# Schematic_GPS_NEOM8N.net
KiCad netlist of a schematic drawn in Altium Designer
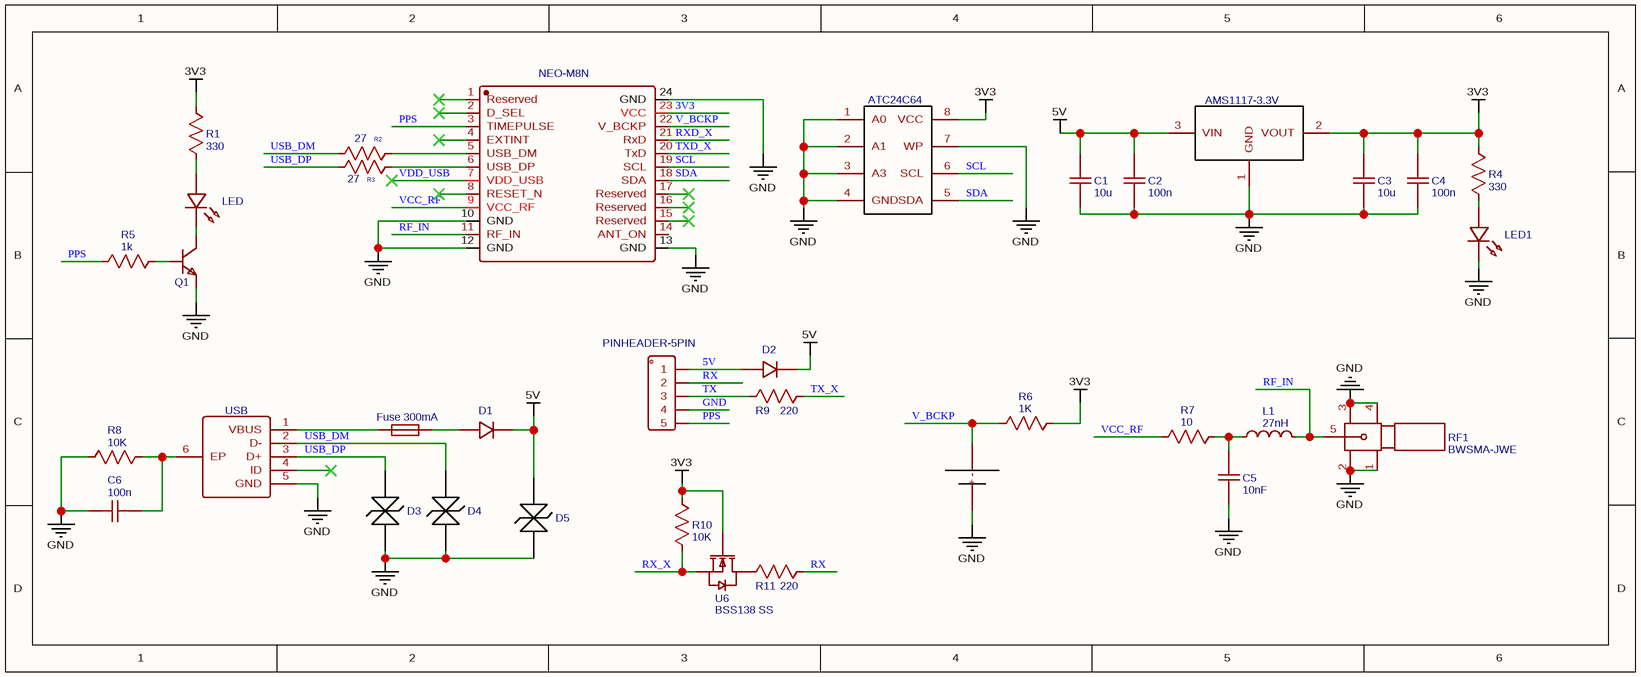
[diagram p0: Schematic_GPS NEOM8N .schdoc]

(export (version "E")
  (design (tool "Eeschema 10.0.6"))
  (components
    (comp (ref "C1")
      (value "10u")
      (fields (field (name "CONTRIBUTOR") "LCEDA_Lib"))
      (libsource (lib "altium-import") (part "root_1_10u_"))
    )
    (comp (ref "C2")
      (value "100n")
      (fields (field (name "CONTRIBUTOR") "LCEDA_Lib"))
      (libsource (lib "altium-import") (part "root_1_100n_"))
    )
    (comp (ref "C3")
      (value "10u")
      (fields (field (name "CONTRIBUTOR") "LCEDA_Lib"))
      (libsource (lib "altium-import") (part "root_1_10u_"))
    )
    (comp (ref "C4")
      (value "100n")
      (fields (field (name "CONTRIBUTOR") "LCEDA_Lib"))
      (libsource (lib "altium-import") (part "root_1_100n_"))
    )
    (comp (ref "C5")
      (value "10nF")
      (fields (field (name "CONTRIBUTOR") "EasyEDA"))
      (libsource (lib "altium-import") (part "root_0_10nF_"))
    )
    (comp (ref "C6")
      (value "100n")
      (fields (field (name "CONTRIBUTOR") "LCEDA_Lib"))
      (libsource (lib "altium-import") (part "root_2_100n_"))
    )
    (comp (ref "CN1")
      (value "PINHEADER-5PIN")
      (fields (field (name "CONTRIBUTOR") "Rebilyn De leon"))
      (libsource (lib "altium-import") (part "root_0_PINHEADER-5PIN_"))
    )
    (comp (ref "D1")
      (value "1N4007W")
      (fields (field (name "MANUFACTURER") "BLUE ROCKET") (field (name "CONTRIBUTOR") "LCEDA_Lib"))
      (libsource (lib "altium-import") (part "root_0_1N4007W_"))
    )
    (comp (ref "D2")
      (value "1N4007W")
      (fields (field (name "MANUFACTURER") "BLUE ROCKET") (field (name "CONTRIBUTOR") "LCEDA_Lib"))
      (libsource (lib "altium-import") (part "root_0_1N4007W_"))
    )
    (comp (ref "D3")
      (value "BI_TVS_DIODE")
      (fields (field (name "CONTRIBUTOR") "Matty87"))
      (libsource (lib "altium-import") (part "root_0_BI_TVS_DIODE_"))
    )
    (comp (ref "D4")
      (value "BI_TVS_DIODE")
      (fields (field (name "CONTRIBUTOR") "Matty87"))
      (libsource (lib "altium-import") (part "root_0_BI_TVS_DIODE_"))
    )
    (comp (ref "D5")
      (value "BI_TVS_DIODE")
      (fields (field (name "CONTRIBUTOR") "Matty87"))
      (libsource (lib "altium-import") (part "root_0_BI_TVS_DIODE_"))
    )
    (comp (ref "L1")
      (value "27nH")
      (fields (field (name "CONTRIBUTOR") "LCEDA_Lib"))
      (libsource (lib "altium-import") (part "root_0_27nH_"))
    )
    (comp (ref "LED")
      (value "LED-0603_R")
      (fields
        (field (name "MANUFACTURER") "EVERLIGHT(台湾亿光)")
        (field (name "MANUFACTURER PART") "19-217/R6C-AL1M2VY/3T")
        (field (name "CONTRIBUTOR") "LCEDA_01")
      )
      (libsource (lib "altium-import") (part "root_3_LED-0603_R_"))
    )
    (comp (ref "LED1")
      (value "LED-0603_R")
      (fields
        (field (name "MANUFACTURER") "EVERLIGHT(台湾亿光)")
        (field (name "MANUFACTURER PART") "19-217/R6C-AL1M2VY/3T")
        (field (name "CONTRIBUTOR") "LCEDA_01")
      )
      (libsource (lib "altium-import") (part "root_3_LED-0603_R_"))
    )
    (comp (ref "Q1")
      (value "2N3904(SOT-23)")
      (fields
        (field (name "MANUFACTURER") "KEC")
        (field (name "MANUFACTURER PART") "2n3904S-RTK/PS")
        (field (name "CONTRIBUTOR") "LCEDA_Lib")
      )
      (libsource (lib "altium-import") (part "root_0_2N3904(SOT-23)_"))
    )
    (comp (ref "R1")
      (value "330")
      (fields (field (name "CONTRIBUTOR") "LCEDA_Lib"))
      (libsource (lib "altium-import") (part "root_1_330_"))
    )
    (comp (ref "R2")
      (value "27")
      (fields (field (name "CONTRIBUTOR") "LCEDA_Lib"))
      (libsource (lib "altium-import") (part "root_0_27_"))
    )
    (comp (ref "R3")
      (value "27")
      (fields (field (name "CONTRIBUTOR") "LCEDA_Lib"))
      (libsource (lib "altium-import") (part "root_0_27_"))
    )
    (comp (ref "R4")
      (value "330")
      (fields (field (name "CONTRIBUTOR") "LCEDA_Lib"))
      (libsource (lib "altium-import") (part "root_1_330_"))
    )
    (comp (ref "R5")
      (value "1k")
      (fields (field (name "CONTRIBUTOR") "LCEDA_Lib"))
      (libsource (lib "altium-import") (part "root_0_1k_"))
    )
    (comp (ref "R6")
      (value "1K")
      (fields (field (name "CONTRIBUTOR") "LCEDA_Lib"))
      (libsource (lib "altium-import") (part "root_2_1K_"))
    )
    (comp (ref "R7")
      (value "10")
      (fields (field (name "CONTRIBUTOR") "LCEDA_Lib"))
      (libsource (lib "altium-import") (part "root_2_10_"))
    )
    (comp (ref "R8")
      (value "10K")
      (fields (field (name "CONTRIBUTOR") "LCEDA_Lib"))
      (libsource (lib "altium-import") (part "root_0_10K_"))
    )
    (comp (ref "R9")
      (value "220")
      (fields (field (name "CONTRIBUTOR") "LCEDA_Lib"))
      (libsource (lib "altium-import") (part "root_0_220_"))
    )
    (comp (ref "R10")
      (value "10K")
      (fields (field (name "CONTRIBUTOR") "LCEDA_Lib"))
      (libsource (lib "altium-import") (part "root_1_10K_"))
    )
    (comp (ref "R11")
      (value "220")
      (fields (field (name "CONTRIBUTOR") "LCEDA_Lib"))
      (libsource (lib "altium-import") (part "root_0_220_"))
    )
    (comp (ref "RF1")
      (value "BWSMA-JWE")
      (fields (field (name "MANUFACTURER") "BAT WIRELESS(蝙蝠无线)") (field (name "CONTRIBUTOR") "ARNABMACH0"))
      (libsource (lib "altium-import") (part "root_0_BWSMA-JWE_"))
    )
    (comp (ref "U1")
      (value "AMS1117-3.3V")
      (fields (field (name "CONTRIBUTOR") "kleity"))
      (libsource (lib "altium-import") (part "root_0_AMS1117-3.3V_"))
    )
    (comp (ref "U2")
      (value "NEO-M8N")
      (fields (field (name "CONTRIBUTOR") "LCSC"))
      (libsource (lib "altium-import") (part "root_0_NEO-M8N_"))
    )
    (comp (ref "U3")
      (value "ATC24C64")
      (fields (field (name "CONTRIBUTOR") "gwranarzary"))
      (libsource (lib "altium-import") (part "root_0_ATC24C64_"))
    )
    (comp (ref "U4")
      (value "Fuse 300mA")
      (fields
        (field (name "MANUFACTURER") "Littelfuse(美国力特)")
        (field (name "MANUFACTURER PART") "1812L110PR")
        (field (name "CONTRIBUTOR") "LCSC")
      )
      (libsource (lib "altium-import") (part "root_0_Fuse 300mA_"))
    )
    (comp (ref "U5")
      (value "AA batery")
      (fields (field (name "CONTRIBUTOR") "tomaskotian"))
      (libsource (lib "altium-import") (part "root_3_AA batery_"))
    )
    (comp (ref "U6")
      (value "BSS138 SS")
      (fields (field (name "MANUFACTURER") "CBI(创基)") (field (name "CONTRIBUTOR") "lcsc"))
      (libsource (lib "altium-import") (part "root_3_BSS138 SS_"))
    )
    (comp (ref "USB")
      (value "BTC-MC5S-43")
      (fields (field (name "MANUFACTURER") "DGBZ(东莞博众)") (field (name "CONTRIBUTOR") "LCSC"))
      (libsource (lib "altium-import") (part "root_0_BTC-MC5S-43_"))
    )
  )
  (nets
    (net (code "1") (name "/PPS") (class "Default")
      (node (ref "CN1") (pin "5") (pinfunction "5_5") (pintype "passive"))
      (node (ref "R5") (pin "1") (pinfunction "1_1") (pintype "passive"))
      (node (ref "U2") (pin "3") (pinfunction "TIMEPULSE_3") (pintype "passive"))
    )
    (net (code "2") (name "/RF_IN") (class "Default")
      (node (ref "L1") (pin "2") (pinfunction "2_2") (pintype "passive"))
      (node (ref "RF1") (pin "5") (pinfunction "5_5") (pintype "passive"))
      (node (ref "U2") (pin "11") (pinfunction "RF_IN_11") (pintype "passive"))
    )
    (net (code "3") (name "/RX") (class "Default")
      (node (ref "CN1") (pin "2") (pinfunction "2_2") (pintype "passive"))
      (node (ref "R11") (pin "2") (pinfunction "2_2") (pintype "passive"))
    )
    (net (code "4") (name "/RXD_X") (class "Default")
      (node (ref "U2") (pin "21") (pinfunction "RxD_21") (pintype "passive"))
    )
    (net (code "5") (name "/RX_X") (class "Default")
      (node (ref "R10") (pin "1") (pinfunction "1_1") (pintype "passive"))
      (node (ref "U6") (pin "2") (pinfunction "S_2") (pintype "passive"))
    )
    (net (code "6") (name "/SCL") (class "Default")
      (node (ref "U2") (pin "19") (pinfunction "SCL_19") (pintype "passive"))
      (node (ref "U3") (pin "6") (pinfunction "SCL_6") (pintype "passive"))
    )
    (net (code "7") (name "/SDA") (class "Default")
      (node (ref "U2") (pin "18") (pinfunction "SDA_18") (pintype "passive"))
      (node (ref "U3") (pin "5") (pinfunction "SDA_5") (pintype "passive"))
    )
    (net (code "8") (name "/TX") (class "Default")
      (node (ref "CN1") (pin "3") (pinfunction "3_3") (pintype "passive"))
      (node (ref "R9") (pin "1") (pinfunction "1_1") (pintype "passive"))
    )
    (net (code "9") (name "/TXD_X") (class "Default")
      (node (ref "U2") (pin "20") (pinfunction "TxD_20") (pintype "passive"))
    )
    (net (code "10") (name "/TX_X") (class "Default")
      (node (ref "R9") (pin "2") (pinfunction "2_2") (pintype "passive"))
    )
    (net (code "11") (name "/USB_DM") (class "Default")
      (node (ref "D4") (pin "1") (pinfunction "1_1") (pintype "passive"))
      (node (ref "R2") (pin "1") (pinfunction "1_1") (pintype "passive"))
      (node (ref "USB") (pin "2") (pinfunction "D-_2") (pintype "passive"))
    )
    (net (code "12") (name "/USB_DP") (class "Default")
      (node (ref "D3") (pin "1") (pinfunction "1_1") (pintype "passive"))
      (node (ref "R3") (pin "1") (pinfunction "1_1") (pintype "passive"))
      (node (ref "USB") (pin "3") (pinfunction "D+_3") (pintype "passive"))
    )
    (net (code "13") (name "/VCC_RF") (class "Default")
      (node (ref "R7") (pin "2") (pinfunction "2_2") (pintype "passive"))
      (node (ref "U2") (pin "9") (pinfunction "VCC_RF_9") (pintype "passive"))
    )
    (net (code "14") (name "/VDD_USB") (class "Default")
      (node (ref "U2") (pin "7") (pinfunction "VDD_USB_7") (pintype "passive+no_connect"))
    )
    (net (code "15") (name "/V_BCKP") (class "Default")
      (node (ref "R6") (pin "2") (pinfunction "2_2") (pintype "passive"))
      (node (ref "U2") (pin "22") (pinfunction "V_BCKP_22") (pintype "passive"))
      (node (ref "U5") (pin "1") (pinfunction "+_1") (pintype "passive"))
    )
    (net (code "16") (name "3V3") (class "Default")
      (node (ref "C3") (pin "2") (pinfunction "2_2") (pintype "passive"))
      (node (ref "C4") (pin "2") (pinfunction "2_2") (pintype "passive"))
      (node (ref "R1") (pin "2") (pinfunction "2_2") (pintype "passive"))
      (node (ref "R10") (pin "2") (pinfunction "2_2") (pintype "passive"))
      (node (ref "R4") (pin "2") (pinfunction "2_2") (pintype "passive"))
      (node (ref "R6") (pin "1") (pinfunction "1_1") (pintype "passive"))
      (node (ref "U1") (pin "2") (pinfunction "VOUT_2") (pintype "passive"))
      (node (ref "U2") (pin "23") (pinfunction "VCC_23") (pintype "passive"))
      (node (ref "U3") (pin "8") (pinfunction "VCC_8") (pintype "passive"))
      (node (ref "U6") (pin "1") (pinfunction "G_1") (pintype "passive"))
    )
    (net (code "17") (name "5V") (class "Default")
      (node (ref "C1") (pin "2") (pinfunction "2_2") (pintype "passive"))
      (node (ref "C2") (pin "2") (pinfunction "2_2") (pintype "passive"))
      (node (ref "CN1") (pin "1") (pinfunction "1_1") (pintype "passive"))
      (node (ref "D1") (pin "1") (pinfunction "1_1") (pintype "passive"))
      (node (ref "D2") (pin "1") (pinfunction "1_1") (pintype "passive"))
      (node (ref "D2") (pin "2") (pinfunction "2_2") (pintype "passive"))
      (node (ref "D5") (pin "1") (pinfunction "1_1") (pintype "passive"))
      (node (ref "U1") (pin "3") (pinfunction "VIN_3") (pintype "passive"))
    )
    (net (code "18") (name "GND") (class "Default")
      (node (ref "C1") (pin "1") (pinfunction "1_1") (pintype "passive"))
      (node (ref "C2") (pin "1") (pinfunction "1_1") (pintype "passive"))
      (node (ref "C3") (pin "1") (pinfunction "1_1") (pintype "passive"))
      (node (ref "C4") (pin "1") (pinfunction "1_1") (pintype "passive"))
      (node (ref "C5") (pin "1") (pinfunction "1_1") (pintype "passive"))
      (node (ref "C6") (pin "2") (pinfunction "2_2") (pintype "passive"))
      (node (ref "CN1") (pin "4") (pinfunction "4_4") (pintype "passive"))
      (node (ref "D3") (pin "2") (pinfunction "2_2") (pintype "passive"))
      (node (ref "D4") (pin "2") (pinfunction "2_2") (pintype "passive"))
      (node (ref "D5") (pin "2") (pinfunction "2_2") (pintype "passive"))
      (node (ref "LED1") (pin "2") (pinfunction "2_2") (pintype "passive"))
      (node (ref "Q1") (pin "1") (pinfunction "E_1") (pintype "passive"))
      (node (ref "R8") (pin "1") (pinfunction "1_1") (pintype "passive"))
      (node (ref "RF1") (pin "1") (pinfunction "1_1") (pintype "passive"))
      (node (ref "RF1") (pin "2") (pinfunction "2_2") (pintype "passive"))
      (node (ref "RF1") (pin "3") (pinfunction "3_3") (pintype "passive"))
      (node (ref "RF1") (pin "4") (pinfunction "4_4") (pintype "passive"))
      (node (ref "U1") (pin "1") (pinfunction "GND_1") (pintype "passive"))
      (node (ref "U2") (pin "10") (pinfunction "GND_10") (pintype "passive"))
      (node (ref "U2") (pin "12") (pinfunction "GND_12") (pintype "passive"))
      (node (ref "U2") (pin "13") (pinfunction "GND_13") (pintype "passive"))
      (node (ref "U2") (pin "24") (pinfunction "GND_24") (pintype "passive"))
      (node (ref "U3") (pin "1") (pinfunction "A0_1") (pintype "passive"))
      (node (ref "U3") (pin "2") (pinfunction "A1_2") (pintype "passive"))
      (node (ref "U3") (pin "3") (pinfunction "A3_3") (pintype "passive"))
      (node (ref "U3") (pin "4") (pinfunction "GND_4") (pintype "passive"))
      (node (ref "U3") (pin "7") (pinfunction "WP_7") (pintype "passive"))
      (node (ref "U5") (pin "2") (pinfunction "-_2") (pintype "passive"))
      (node (ref "USB") (pin "5") (pinfunction "GND_5") (pintype "passive"))
    )
    (net (code "19") (name "Net-(C5-Pad2)") (class "Default")
      (node (ref "C5") (pin "2") (pinfunction "2_2") (pintype "passive"))
      (node (ref "L1") (pin "1") (pinfunction "1_1") (pintype "passive"))
      (node (ref "R7") (pin "1") (pinfunction "1_1") (pintype "passive"))
    )
    (net (code "20") (name "Net-(D1-Pad2)") (class "Default")
      (node (ref "D1") (pin "2") (pinfunction "2_2") (pintype "passive"))
      (node (ref "U4") (pin "2") (pinfunction "2_2") (pintype "passive"))
    )
    (net (code "21") (name "Net-(LED-Pad1)") (class "Default")
      (node (ref "LED") (pin "1") (pinfunction "1_1") (pintype "passive"))
      (node (ref "R1") (pin "1") (pinfunction "1_1") (pintype "passive"))
    )
    (net (code "22") (name "Net-(LED1-Pad1)") (class "Default")
      (node (ref "LED1") (pin "1") (pinfunction "1_1") (pintype "passive"))
      (node (ref "R4") (pin "1") (pinfunction "1_1") (pintype "passive"))
    )
    (net (code "23") (name "Net-(Q1-B)") (class "Default")
      (node (ref "Q1") (pin "2") (pinfunction "B_2") (pintype "passive"))
      (node (ref "R5") (pin "2") (pinfunction "2_2") (pintype "passive"))
    )
    (net (code "24") (name "Net-(Q1-C)") (class "Default")
      (node (ref "LED") (pin "2") (pinfunction "2_2") (pintype "passive"))
      (node (ref "Q1") (pin "3") (pinfunction "C_3") (pintype "passive"))
    )
    (net (code "25") (name "Net-(U2-USB_DM)") (class "Default")
      (node (ref "R2") (pin "2") (pinfunction "2_2") (pintype "passive"))
      (node (ref "U2") (pin "5") (pinfunction "USB_DM_5") (pintype "passive"))
    )
    (net (code "26") (name "Net-(U2-USB_DP)") (class "Default")
      (node (ref "R3") (pin "2") (pinfunction "2_2") (pintype "passive"))
      (node (ref "U2") (pin "6") (pinfunction "USB_DP_6") (pintype "passive"))
    )
    (net (code "27") (name "Net-(U6-D)") (class "Default")
      (node (ref "R11") (pin "1") (pinfunction "1_1") (pintype "passive"))
      (node (ref "U6") (pin "3") (pinfunction "D_3") (pintype "passive"))
    )
    (net (code "28") (name "Net-(USB-EP)") (class "Default")
      (node (ref "C6") (pin "1") (pinfunction "1_1") (pintype "passive"))
      (node (ref "R8") (pin "2") (pinfunction "2_2") (pintype "passive"))
      (node (ref "USB") (pin "6") (pinfunction "EP_6") (pintype "passive"))
    )
    (net (code "29") (name "Net-(USB-VBUS)") (class "Default")
      (node (ref "U4") (pin "1") (pinfunction "1_1") (pintype "passive"))
      (node (ref "USB") (pin "1") (pinfunction "VBUS_1") (pintype "passive"))
    )
    (net (code "30") (name "unconnected-(U2-ANT_ON-Pad14)") (class "Default")
      (node (ref "U2") (pin "14") (pinfunction "ANT_ON_14") (pintype "passive"))
    )
    (net (code "31") (name "unconnected-(U2-D_SEL-Pad2)") (class "Default")
      (node (ref "U2") (pin "2") (pinfunction "D_SEL_2") (pintype "passive+no_connect"))
    )
    (net (code "32") (name "unconnected-(U2-EXTINT-Pad4)") (class "Default")
      (node (ref "U2") (pin "4") (pinfunction "EXTINT_4") (pintype "passive+no_connect"))
    )
    (net (code "33") (name "unconnected-(U2-RESET_N-Pad8)") (class "Default")
      (node (ref "U2") (pin "8") (pinfunction "RESET_N_8") (pintype "passive+no_connect"))
    )
    (net (code "34") (name "unconnected-(U2-Reserved-Pad1)") (class "Default")
      (node (ref "U2") (pin "1") (pinfunction "Reserved_1") (pintype "passive+no_connect"))
    )
    (net (code "35") (name "unconnected-(U2-Reserved-Pad15)") (class "Default")
      (node (ref "U2") (pin "15") (pinfunction "Reserved_15") (pintype "passive+no_connect"))
    )
    (net (code "36") (name "unconnected-(U2-Reserved-Pad16)") (class "Default")
      (node (ref "U2") (pin "16") (pinfunction "Reserved_16") (pintype "passive+no_connect"))
    )
    (net (code "37") (name "unconnected-(U2-Reserved-Pad17)") (class "Default")
      (node (ref "U2") (pin "17") (pinfunction "Reserved_17") (pintype "passive+no_connect"))
    )
    (net (code "38") (name "unconnected-(USB-ID-Pad4)") (class "Default")
      (node (ref "USB") (pin "4") (pinfunction "ID_4") (pintype "passive+no_connect"))
    )
  )
)
